# IR_detector.net
KiCad netlist of a schematic drawn in EAGLE
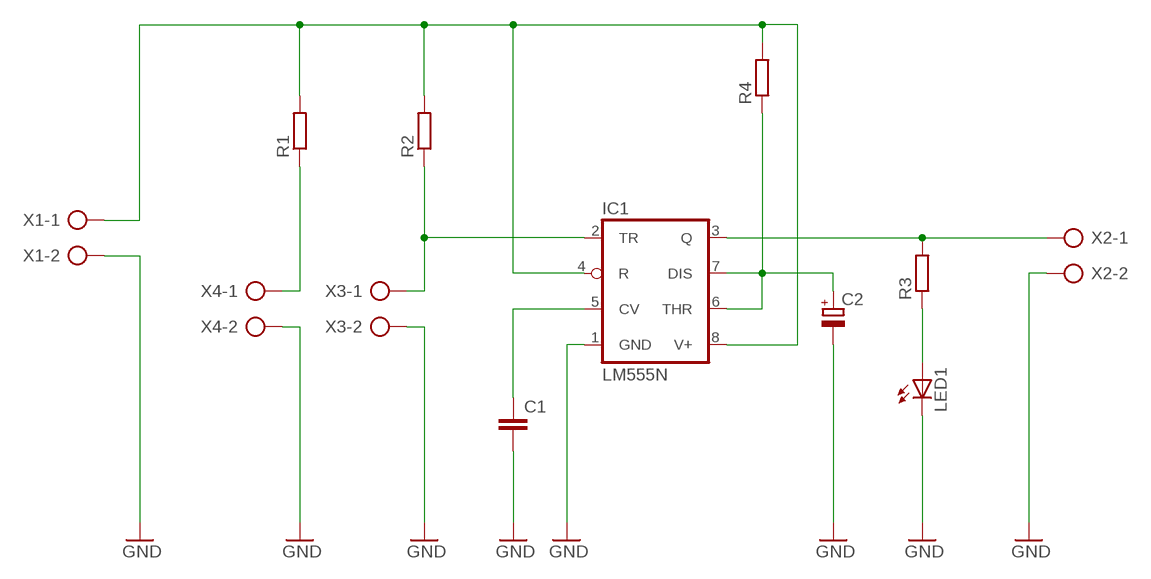
[diagram p0: schematic, sheet 1]

(export (version "E")
  (design (tool "Eeschema 10.0.6"))
  (components
    (comp (ref "C1")
      (value "C-EU050-030X075")
      (footprint "eagle-import:C050-030X075")
      (libsource (lib "eagle-import") (part "C-EU050-030X075"))
    )
    (comp (ref "C2")
      (value "CPOL-EUE5-8.5")
      (footprint "eagle-import:E5-8,5")
      (libsource (lib "eagle-import") (part "CPOL-EUE5-8.5"))
    )
    (comp (ref "IC1")
      (value "LM555N")
      (footprint "eagle-import:DIL08")
      (libsource (lib "eagle-import") (part "555NLM"))
    )
    (comp (ref "LED1")
      (value "LED-LUMILED")
      (footprint "eagle-import:LUMILED")
      (libsource (lib "eagle-import") (part "LED-LUMILED"))
    )
    (comp (ref "R1")
      (value "R-EU_0204/7")
      (footprint "eagle-import:0204_7")
      (libsource (lib "eagle-import") (part "R-EU_0204/7"))
    )
    (comp (ref "R2")
      (value "R-EU_0204/7")
      (footprint "eagle-import:0204_7")
      (libsource (lib "eagle-import") (part "R-EU_0204/7"))
    )
    (comp (ref "R3")
      (value "R-EU_0204/7")
      (footprint "eagle-import:0204_7")
      (libsource (lib "eagle-import") (part "R-EU_0204/7"))
    )
    (comp (ref "R4")
      (value "R-EU_0204/7")
      (footprint "eagle-import:0204_7")
      (libsource (lib "eagle-import") (part "R-EU_0204/7"))
    )
    (comp (ref "X1")
      (value "AK300/2")
      (footprint "eagle-import:AK300_2")
      (libsource (lib "eagle-import") (part "AK300/2"))
    )
    (comp (ref "X2")
      (value "AK300/2")
      (footprint "eagle-import:AK300_2")
      (libsource (lib "eagle-import") (part "AK300/2"))
    )
    (comp (ref "X3")
      (value "AK300/2")
      (footprint "eagle-import:AK300_2")
      (libsource (lib "eagle-import") (part "AK300/2"))
    )
    (comp (ref "X4")
      (value "AK300/2")
      (footprint "eagle-import:AK300_2")
      (libsource (lib "eagle-import") (part "AK300/2"))
    )
  )
  (nets
    (net (code "1") (name "GND") (class "Default")
      (node (ref "C1") (pin "2") (pinfunction "2_2") (pintype "passive"))
      (node (ref "C2") (pin "-") (pinfunction "-_-") (pintype "passive"))
      (node (ref "IC1") (pin "1") (pinfunction "GND_1") (pintype "power_in"))
      (node (ref "LED1") (pin "4-") (pinfunction "C_4-") (pintype "passive"))
      (node (ref "X1") (pin "2") (pinfunction "KL_2") (pintype "passive"))
      (node (ref "X2") (pin "2") (pinfunction "KL_2") (pintype "passive"))
      (node (ref "X3") (pin "2") (pinfunction "KL_2") (pintype "passive"))
      (node (ref "X4") (pin "2") (pinfunction "KL_2") (pintype "passive"))
    )
    (net (code "2") (name "Net-(IC1-CV)") (class "Default")
      (node (ref "C1") (pin "1") (pinfunction "1_1") (pintype "passive"))
      (node (ref "IC1") (pin "5") (pinfunction "CV_5") (pintype "input"))
    )
    (net (code "3") (name "Net-(IC1-DIS)") (class "Default")
      (node (ref "C2") (pin "+") (pinfunction "+_+") (pintype "passive"))
      (node (ref "IC1") (pin "6") (pinfunction "THR_6") (pintype "input"))
      (node (ref "IC1") (pin "7") (pinfunction "DIS_7") (pintype "input"))
      (node (ref "R4") (pin "1") (pinfunction "1_1") (pintype "passive"))
    )
    (net (code "4") (name "Net-(IC1-Q)") (class "Default")
      (node (ref "IC1") (pin "3") (pinfunction "Q_3") (pintype "output"))
      (node (ref "R3") (pin "2") (pinfunction "2_2") (pintype "passive"))
      (node (ref "X2") (pin "1") (pinfunction "KL_1") (pintype "passive"))
    )
    (net (code "5") (name "Net-(IC1-R)") (class "Default")
      (node (ref "IC1") (pin "4") (pinfunction "R_4") (pintype "input"))
      (node (ref "IC1") (pin "8") (pinfunction "V+_8") (pintype "power_in"))
      (node (ref "R1") (pin "2") (pinfunction "2_2") (pintype "passive"))
      (node (ref "R2") (pin "2") (pinfunction "2_2") (pintype "passive"))
      (node (ref "R4") (pin "2") (pinfunction "2_2") (pintype "passive"))
      (node (ref "X1") (pin "1") (pinfunction "KL_1") (pintype "passive"))
    )
    (net (code "6") (name "Net-(IC1-TR)") (class "Default")
      (node (ref "IC1") (pin "2") (pinfunction "TR_2") (pintype "input"))
      (node (ref "R2") (pin "1") (pinfunction "1_1") (pintype "passive"))
      (node (ref "X3") (pin "1") (pinfunction "KL_1") (pintype "passive"))
    )
    (net (code "7") (name "Net-(LED1-A)") (class "Default")
      (node (ref "LED1") (pin "2+") (pinfunction "A_2+") (pintype "passive"))
      (node (ref "R3") (pin "1") (pinfunction "1_1") (pintype "passive"))
    )
    (net (code "8") (name "Net-(X4A-KL)") (class "Default")
      (node (ref "R1") (pin "1") (pinfunction "1_1") (pintype "passive"))
      (node (ref "X4") (pin "1") (pinfunction "KL_1") (pintype "passive"))
    )
  )
)
